# XMC4800-Misc.net
KiCad netlist of a schematic drawn in Altium Designer
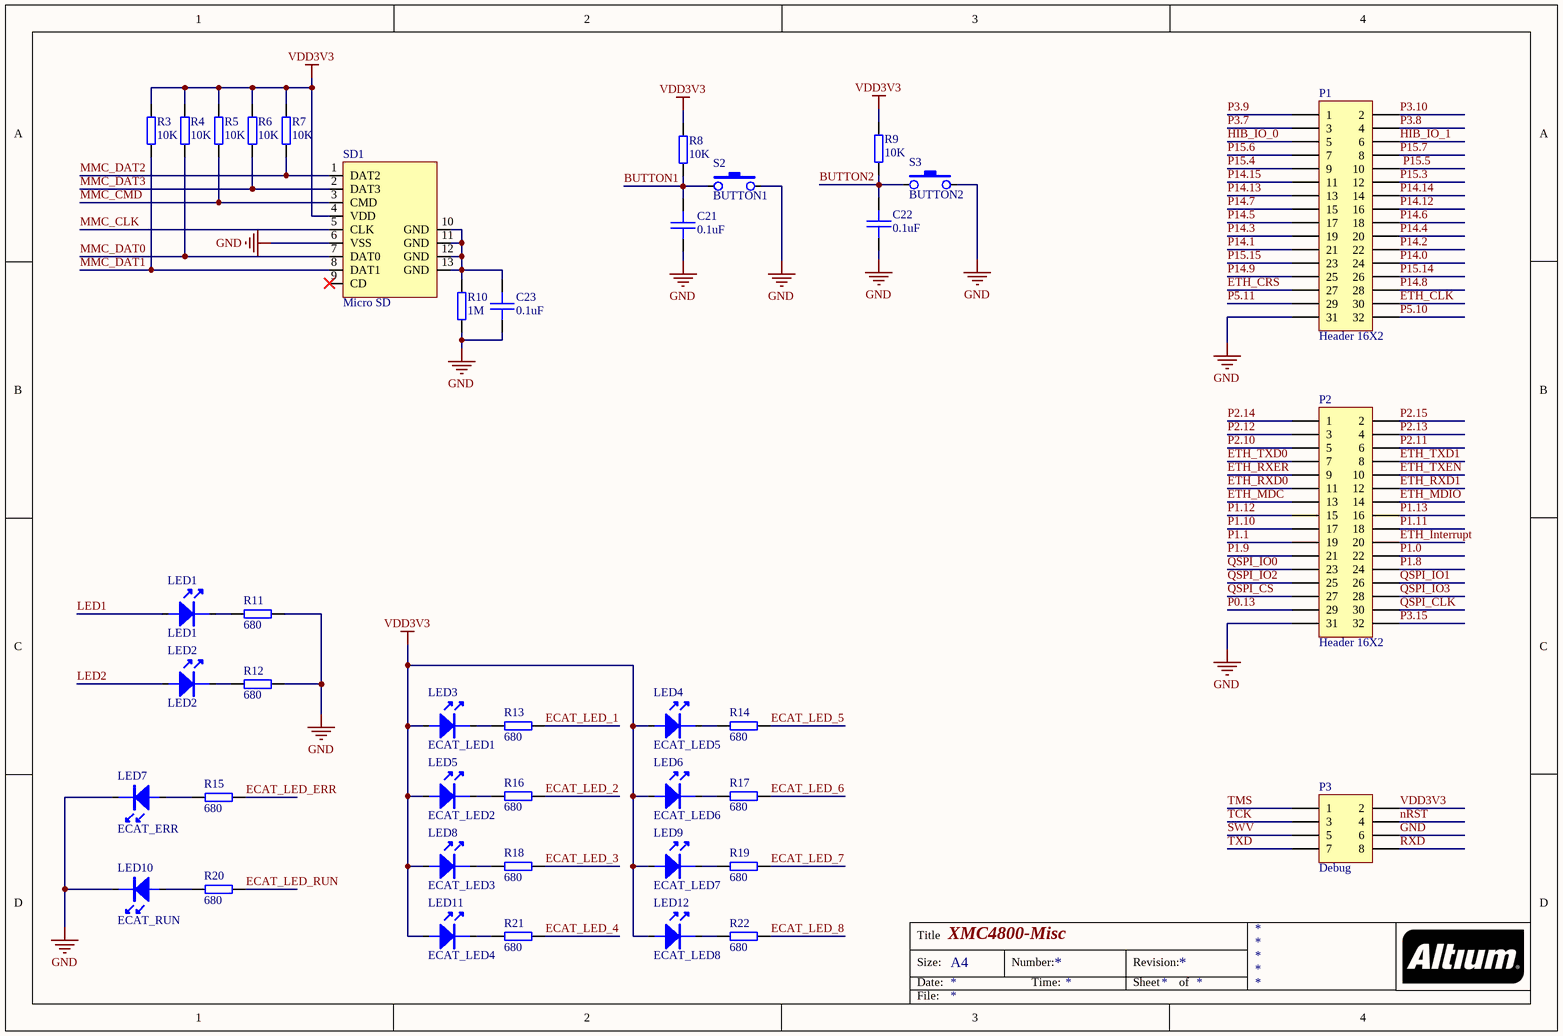
[diagram p0: XMC4800-Misc.SchDoc]

(export (version "E")
  (design (tool "Eeschema 10.0.6"))
  (components
    (comp (ref "C21")
      (value "0.1uF")
      (footprint "CAP-0603")
      (description "陶瓷贴片电容0603")
      (fields (field (name "TOLERANCE") "10%") (field (name "VOLTAGE") "50V"))
      (libsource (lib "momo") (part "C_0603"))
    )
    (comp (ref "C22")
      (value "0.1uF")
      (footprint "CAP-0603")
      (description "陶瓷贴片电容0603")
      (fields (field (name "TOLERANCE") "10%") (field (name "VOLTAGE") "50V"))
      (libsource (lib "momo") (part "C_0603"))
    )
    (comp (ref "C23")
      (value "0.1uF")
      (footprint "CAP-0603")
      (description "陶瓷贴片电容0603")
      (fields (field (name "TOLERANCE") "10%") (field (name "VOLTAGE") "50V"))
      (libsource (lib "momo") (part "C_0603"))
    )
    (comp (ref "LED1")
      (value "LED1")
      (footprint "LED_0603")
      (description "0603封装发光二极管")
      (libsource (lib "momo") (part "LED_0603"))
    )
    (comp (ref "LED2")
      (value "LED2")
      (footprint "LED_0603")
      (description "0603封装发光二极管")
      (libsource (lib "momo") (part "LED_0603"))
    )
    (comp (ref "LED3")
      (value "ECAT_LED1")
      (footprint "LED_0603")
      (description "0603封装发光二极管")
      (libsource (lib "momo") (part "LED_0603"))
    )
    (comp (ref "LED4")
      (value "ECAT_LED5")
      (footprint "LED_0603")
      (description "0603封装发光二极管")
      (libsource (lib "momo") (part "LED_0603"))
    )
    (comp (ref "LED5")
      (value "ECAT_LED2")
      (footprint "LED_0603")
      (description "0603封装发光二极管")
      (libsource (lib "momo") (part "LED_0603"))
    )
    (comp (ref "LED6")
      (value "ECAT_LED6")
      (footprint "LED_0603")
      (description "0603封装发光二极管")
      (libsource (lib "momo") (part "LED_0603"))
    )
    (comp (ref "LED7")
      (value "ECAT_ERR")
      (footprint "P-LCC-2")
      (description "3528封装发光二极管")
      (libsource (lib "momo") (part "LED_3528"))
    )
    (comp (ref "LED8")
      (value "ECAT_LED3")
      (footprint "LED_0603")
      (description "0603封装发光二极管")
      (libsource (lib "momo") (part "LED_0603"))
    )
    (comp (ref "LED9")
      (value "ECAT_LED7")
      (footprint "LED_0603")
      (description "0603封装发光二极管")
      (libsource (lib "momo") (part "LED_0603"))
    )
    (comp (ref "LED10")
      (value "ECAT_RUN")
      (footprint "P-LCC-2")
      (description "3528封装发光二极管")
      (libsource (lib "momo") (part "LED_3528"))
    )
    (comp (ref "LED11")
      (value "ECAT_LED4")
      (footprint "LED_0603")
      (description "0603封装发光二极管")
      (libsource (lib "momo") (part "LED_0603"))
    )
    (comp (ref "LED12")
      (value "ECAT_LED8")
      (footprint "LED_0603")
      (description "0603封装发光二极管")
      (libsource (lib "momo") (part "LED_0603"))
    )
    (comp (ref "P1")
      (value "Header 16X2")
      (footprint "HDR2X16")
      (description "Header, 16-Pin, Dual row")
      (fields (field (name "PUBLISHER") "Altium Limited"))
      (libsource (lib "Miscellaneous Connectors") (part "Header 16X2"))
    )
    (comp (ref "P2")
      (value "Header 16X2")
      (footprint "HDR2X16")
      (description "Header, 16-Pin, Dual row")
      (fields (field (name "PUBLISHER") "Altium Limited"))
      (libsource (lib "Miscellaneous Connectors") (part "Header 16X2"))
    )
    (comp (ref "P3")
      (value "Debug")
      (footprint "HDR2X4")
      (description "Header, 4-Pin, Dual row")
      (fields (field (name "PUBLISHER") "Altium Limited"))
      (libsource (lib "Miscellaneous Connectors") (part "Header 4X2"))
    )
    (comp (ref "R3")
      (value "10K")
      (footprint "RES-0603")
      (description "贴片电阻0603")
      (fields (field (name "TOLERANCE") "5%") (field (name "VOLTAGE") "50V"))
      (libsource (lib "momo") (part "R_0603"))
    )
    (comp (ref "R4")
      (value "10K")
      (footprint "RES-0603")
      (description "贴片电阻0603")
      (fields (field (name "TOLERANCE") "5%") (field (name "VOLTAGE") "50V"))
      (libsource (lib "momo") (part "R_0603"))
    )
    (comp (ref "R5")
      (value "10K")
      (footprint "RES-0603")
      (description "贴片电阻0603")
      (fields (field (name "TOLERANCE") "5%") (field (name "VOLTAGE") "50V"))
      (libsource (lib "momo") (part "R_0603"))
    )
    (comp (ref "R6")
      (value "10K")
      (footprint "RES-0603")
      (description "贴片电阻0603")
      (fields (field (name "TOLERANCE") "5%") (field (name "VOLTAGE") "50V"))
      (libsource (lib "momo") (part "R_0603"))
    )
    (comp (ref "R7")
      (value "10K")
      (footprint "RES-0603")
      (description "贴片电阻0603")
      (fields (field (name "TOLERANCE") "5%") (field (name "VOLTAGE") "50V"))
      (libsource (lib "momo") (part "R_0603"))
    )
    (comp (ref "R8")
      (value "10K")
      (footprint "RES-0603")
      (description "贴片电阻0603")
      (fields (field (name "TOLERANCE") "5%") (field (name "VOLTAGE") "50V"))
      (libsource (lib "momo") (part "R_0603"))
    )
    (comp (ref "R9")
      (value "10K")
      (footprint "RES-0603")
      (description "贴片电阻0603")
      (fields (field (name "TOLERANCE") "5%") (field (name "VOLTAGE") "50V"))
      (libsource (lib "momo") (part "R_0603"))
    )
    (comp (ref "R10")
      (value "1M")
      (footprint "RES-0603")
      (description "贴片电阻0603")
      (fields (field (name "TOLERANCE") "5%") (field (name "VOLTAGE") "50V"))
      (libsource (lib "momo") (part "R_0603"))
    )
    (comp (ref "R11")
      (value "680")
      (footprint "RES-0603")
      (description "贴片电阻0603")
      (fields (field (name "TOLERANCE") "5%") (field (name "VOLTAGE") "50V"))
      (libsource (lib "momo") (part "R_0603"))
    )
    (comp (ref "R12")
      (value "680")
      (footprint "RES-0603")
      (description "贴片电阻0603")
      (fields (field (name "TOLERANCE") "5%") (field (name "VOLTAGE") "50V"))
      (libsource (lib "momo") (part "R_0603"))
    )
    (comp (ref "R13")
      (value "680")
      (footprint "RES-0603")
      (description "贴片电阻0603")
      (fields (field (name "TOLERANCE") "5%") (field (name "VOLTAGE") "50V"))
      (libsource (lib "momo") (part "R_0603"))
    )
    (comp (ref "R14")
      (value "680")
      (footprint "RES-0603")
      (description "贴片电阻0603")
      (fields (field (name "TOLERANCE") "5%") (field (name "VOLTAGE") "50V"))
      (libsource (lib "momo") (part "R_0603"))
    )
    (comp (ref "R15")
      (value "680")
      (footprint "RES-0603")
      (description "贴片电阻0603")
      (fields (field (name "TOLERANCE") "5%") (field (name "VOLTAGE") "50V"))
      (libsource (lib "momo") (part "R_0603"))
    )
    (comp (ref "R16")
      (value "680")
      (footprint "RES-0603")
      (description "贴片电阻0603")
      (fields (field (name "TOLERANCE") "5%") (field (name "VOLTAGE") "50V"))
      (libsource (lib "momo") (part "R_0603"))
    )
    (comp (ref "R17")
      (value "680")
      (footprint "RES-0603")
      (description "贴片电阻0603")
      (fields (field (name "TOLERANCE") "5%") (field (name "VOLTAGE") "50V"))
      (libsource (lib "momo") (part "R_0603"))
    )
    (comp (ref "R18")
      (value "680")
      (footprint "RES-0603")
      (description "贴片电阻0603")
      (fields (field (name "TOLERANCE") "5%") (field (name "VOLTAGE") "50V"))
      (libsource (lib "momo") (part "R_0603"))
    )
    (comp (ref "R19")
      (value "680")
      (footprint "RES-0603")
      (description "贴片电阻0603")
      (fields (field (name "TOLERANCE") "5%") (field (name "VOLTAGE") "50V"))
      (libsource (lib "momo") (part "R_0603"))
    )
    (comp (ref "R20")
      (value "680")
      (footprint "RES-0603")
      (description "贴片电阻0603")
      (fields (field (name "TOLERANCE") "5%") (field (name "VOLTAGE") "50V"))
      (libsource (lib "momo") (part "R_0603"))
    )
    (comp (ref "R21")
      (value "680")
      (footprint "RES-0603")
      (description "贴片电阻0603")
      (fields (field (name "TOLERANCE") "5%") (field (name "VOLTAGE") "50V"))
      (libsource (lib "momo") (part "R_0603"))
    )
    (comp (ref "R22")
      (value "680")
      (footprint "RES-0603")
      (description "贴片电阻0603")
      (fields (field (name "TOLERANCE") "5%") (field (name "VOLTAGE") "50V"))
      (libsource (lib "momo") (part "R_0603"))
    )
    (comp (ref "S2")
      (value "BUTTON1")
      (footprint "KEY_3X4X2")
      (description "轻触开关3X4X2")
      (libsource (lib "momo") (part "KEY"))
    )
    (comp (ref "S3")
      (value "BUTTON2")
      (footprint "KEY_3X4X2")
      (description "轻触开关3X4X2")
      (libsource (lib "momo") (part "KEY"))
    )
    (comp (ref "SD1")
      (value "Micro SD")
      (footprint "7MSDP-B0-1012")
      (description "Micro SD卡座")
      (libsource (lib "momo") (part "Micro SD"))
    )
  )
  (nets
    (net (code "1") (name "/BUTTON1") (class "Default")
      (node (ref "C21") (pin "1") (pinfunction "1_1") (pintype "passive"))
      (node (ref "R8") (pin "1") (pinfunction "1_1") (pintype "passive"))
      (node (ref "S2") (pin "1") (pinfunction "1_1") (pintype "passive"))
    )
    (net (code "2") (name "/BUTTON2") (class "Default")
      (node (ref "C22") (pin "1") (pinfunction "1_1") (pintype "passive"))
      (node (ref "R9") (pin "1") (pinfunction "1_1") (pintype "passive"))
      (node (ref "S3") (pin "1") (pinfunction "1_1") (pintype "passive"))
    )
    (net (code "3") (name "/ECAT_LED_1") (class "Default")
      (node (ref "R13") (pin "2") (pinfunction "2_2") (pintype "passive"))
    )
    (net (code "4") (name "/ECAT_LED_2") (class "Default")
      (node (ref "R16") (pin "2") (pinfunction "2_2") (pintype "passive"))
    )
    (net (code "5") (name "/ECAT_LED_3") (class "Default")
      (node (ref "R18") (pin "2") (pinfunction "2_2") (pintype "passive"))
    )
    (net (code "6") (name "/ECAT_LED_4") (class "Default")
      (node (ref "R21") (pin "2") (pinfunction "2_2") (pintype "passive"))
    )
    (net (code "7") (name "/ECAT_LED_5") (class "Default")
      (node (ref "R14") (pin "2") (pinfunction "2_2") (pintype "passive"))
    )
    (net (code "8") (name "/ECAT_LED_6") (class "Default")
      (node (ref "R17") (pin "2") (pinfunction "2_2") (pintype "passive"))
    )
    (net (code "9") (name "/ECAT_LED_7") (class "Default")
      (node (ref "R19") (pin "2") (pinfunction "2_2") (pintype "passive"))
    )
    (net (code "10") (name "/ECAT_LED_8") (class "Default")
      (node (ref "R22") (pin "2") (pinfunction "2_2") (pintype "passive"))
    )
    (net (code "11") (name "/ECAT_LED_ERR") (class "Default")
      (node (ref "R15") (pin "2") (pinfunction "2_2") (pintype "passive"))
    )
    (net (code "12") (name "/ECAT_LED_RUN") (class "Default")
      (node (ref "R20") (pin "2") (pinfunction "2_2") (pintype "passive"))
    )
    (net (code "13") (name "/ETH_CLK") (class "Default")
      (node (ref "P1") (pin "30") (pinfunction "30_30") (pintype "passive"))
    )
    (net (code "14") (name "/ETH_CRS") (class "Default")
      (node (ref "P1") (pin "27") (pinfunction "27_27") (pintype "passive"))
    )
    (net (code "15") (name "/ETH_Interrupt") (class "Default")
      (node (ref "P2") (pin "20") (pinfunction "20_20") (pintype "passive"))
    )
    (net (code "16") (name "/ETH_MDC") (class "Default")
      (node (ref "P2") (pin "13") (pinfunction "13_13") (pintype "passive"))
    )
    (net (code "17") (name "/ETH_MDIO") (class "Default")
      (node (ref "P2") (pin "14") (pinfunction "14_14") (pintype "passive"))
    )
    (net (code "18") (name "/ETH_RXD0") (class "Default")
      (node (ref "P2") (pin "11") (pinfunction "11_11") (pintype "passive"))
    )
    (net (code "19") (name "/ETH_RXD1") (class "Default")
      (node (ref "P2") (pin "12") (pinfunction "12_12") (pintype "passive"))
    )
    (net (code "20") (name "/ETH_RXER") (class "Default")
      (node (ref "P2") (pin "9") (pinfunction "9_9") (pintype "passive"))
    )
    (net (code "21") (name "/ETH_TXD0") (class "Default")
      (node (ref "P2") (pin "7") (pinfunction "7_7") (pintype "passive"))
    )
    (net (code "22") (name "/ETH_TXD1") (class "Default")
      (node (ref "P2") (pin "8") (pinfunction "8_8") (pintype "passive"))
    )
    (net (code "23") (name "/ETH_TXEN") (class "Default")
      (node (ref "P2") (pin "10") (pinfunction "10_10") (pintype "passive"))
    )
    (net (code "24") (name "/HIB_IO_0") (class "Default")
      (node (ref "P1") (pin "5") (pinfunction "5_5") (pintype "passive"))
    )
    (net (code "25") (name "/HIB_IO_1") (class "Default")
      (node (ref "P1") (pin "6") (pinfunction "6_6") (pintype "passive"))
    )
    (net (code "26") (name "/LED1") (class "Default")
      (node (ref "LED1") (pin "1") (pinfunction "A_1") (pintype "passive"))
    )
    (net (code "27") (name "/LED2") (class "Default")
      (node (ref "LED2") (pin "1") (pinfunction "A_1") (pintype "passive"))
    )
    (net (code "28") (name "/MMC_CLK") (class "Default")
      (node (ref "SD1") (pin "5") (pinfunction "CLK_5") (pintype "passive"))
    )
    (net (code "29") (name "/MMC_CMD") (class "Default")
      (node (ref "R5") (pin "1") (pinfunction "1_1") (pintype "passive"))
      (node (ref "SD1") (pin "3") (pinfunction "CMD_3") (pintype "passive"))
    )
    (net (code "30") (name "/MMC_DAT0") (class "Default")
      (node (ref "R4") (pin "1") (pinfunction "1_1") (pintype "passive"))
      (node (ref "SD1") (pin "7") (pinfunction "DAT0_7") (pintype "passive"))
    )
    (net (code "31") (name "/MMC_DAT1") (class "Default")
      (node (ref "R3") (pin "1") (pinfunction "1_1") (pintype "passive"))
      (node (ref "SD1") (pin "8") (pinfunction "DAT1_8") (pintype "passive"))
    )
    (net (code "32") (name "/MMC_DAT2") (class "Default")
      (node (ref "R7") (pin "1") (pinfunction "1_1") (pintype "passive"))
      (node (ref "SD1") (pin "1") (pinfunction "DAT2_1") (pintype "passive"))
    )
    (net (code "33") (name "/MMC_DAT3") (class "Default")
      (node (ref "R6") (pin "1") (pinfunction "1_1") (pintype "passive"))
      (node (ref "SD1") (pin "2") (pinfunction "DAT3_2") (pintype "passive"))
    )
    (net (code "34") (name "/P0.13") (class "Default")
      (node (ref "P2") (pin "29") (pinfunction "29_29") (pintype "passive"))
    )
    (net (code "35") (name "/P1.0") (class "Default")
      (node (ref "P2") (pin "22") (pinfunction "22_22") (pintype "passive"))
    )
    (net (code "36") (name "/P1.1") (class "Default")
      (node (ref "P2") (pin "19") (pinfunction "19_19") (pintype "passive"))
    )
    (net (code "37") (name "/P1.8") (class "Default")
      (node (ref "P2") (pin "24") (pinfunction "24_24") (pintype "passive"))
    )
    (net (code "38") (name "/P1.9") (class "Default")
      (node (ref "P2") (pin "21") (pinfunction "21_21") (pintype "passive"))
    )
    (net (code "39") (name "/P1.10") (class "Default")
      (node (ref "P2") (pin "17") (pinfunction "17_17") (pintype "passive"))
    )
    (net (code "40") (name "/P1.11") (class "Default")
      (node (ref "P2") (pin "18") (pinfunction "18_18") (pintype "passive"))
    )
    (net (code "41") (name "/P1.12") (class "Default")
      (node (ref "P2") (pin "15") (pinfunction "15_15") (pintype "passive"))
    )
    (net (code "42") (name "/P1.13") (class "Default")
      (node (ref "P2") (pin "16") (pinfunction "16_16") (pintype "passive"))
    )
    (net (code "43") (name "/P2.10") (class "Default")
      (node (ref "P2") (pin "5") (pinfunction "5_5") (pintype "passive"))
    )
    (net (code "44") (name "/P2.11") (class "Default")
      (node (ref "P2") (pin "6") (pinfunction "6_6") (pintype "passive"))
    )
    (net (code "45") (name "/P2.12") (class "Default")
      (node (ref "P2") (pin "3") (pinfunction "3_3") (pintype "passive"))
    )
    (net (code "46") (name "/P2.13") (class "Default")
      (node (ref "P2") (pin "4") (pinfunction "4_4") (pintype "passive"))
    )
    (net (code "47") (name "/P2.14") (class "Default")
      (node (ref "P2") (pin "1") (pinfunction "1_1") (pintype "passive"))
    )
    (net (code "48") (name "/P2.15") (class "Default")
      (node (ref "P2") (pin "2") (pinfunction "2_2") (pintype "passive"))
    )
    (net (code "49") (name "/P3.7") (class "Default")
      (node (ref "P1") (pin "3") (pinfunction "3_3") (pintype "passive"))
    )
    (net (code "50") (name "/P3.8") (class "Default")
      (node (ref "P1") (pin "4") (pinfunction "4_4") (pintype "passive"))
    )
    (net (code "51") (name "/P3.9") (class "Default")
      (node (ref "P1") (pin "1") (pinfunction "1_1") (pintype "passive"))
    )
    (net (code "52") (name "/P3.10") (class "Default")
      (node (ref "P1") (pin "2") (pinfunction "2_2") (pintype "passive"))
    )
    (net (code "53") (name "/P3.15") (class "Default")
      (node (ref "P2") (pin "32") (pinfunction "32_32") (pintype "passive"))
    )
    (net (code "54") (name "/P5.10") (class "Default")
      (node (ref "P1") (pin "32") (pinfunction "32_32") (pintype "passive"))
    )
    (net (code "55") (name "/P5.11") (class "Default")
      (node (ref "P1") (pin "29") (pinfunction "29_29") (pintype "passive"))
    )
    (net (code "56") (name "/P14.0") (class "Default")
      (node (ref "P1") (pin "24") (pinfunction "24_24") (pintype "passive"))
    )
    (net (code "57") (name "/P14.1") (class "Default")
      (node (ref "P1") (pin "21") (pinfunction "21_21") (pintype "passive"))
    )
    (net (code "58") (name "/P14.2") (class "Default")
      (node (ref "P1") (pin "22") (pinfunction "22_22") (pintype "passive"))
    )
    (net (code "59") (name "/P14.3") (class "Default")
      (node (ref "P1") (pin "19") (pinfunction "19_19") (pintype "passive"))
    )
    (net (code "60") (name "/P14.4") (class "Default")
      (node (ref "P1") (pin "20") (pinfunction "20_20") (pintype "passive"))
    )
    (net (code "61") (name "/P14.5") (class "Default")
      (node (ref "P1") (pin "17") (pinfunction "17_17") (pintype "passive"))
    )
    (net (code "62") (name "/P14.6") (class "Default")
      (node (ref "P1") (pin "18") (pinfunction "18_18") (pintype "passive"))
    )
    (net (code "63") (name "/P14.7") (class "Default")
      (node (ref "P1") (pin "15") (pinfunction "15_15") (pintype "passive"))
    )
    (net (code "64") (name "/P14.8") (class "Default")
      (node (ref "P1") (pin "28") (pinfunction "28_28") (pintype "passive"))
    )
    (net (code "65") (name "/P14.9") (class "Default")
      (node (ref "P1") (pin "25") (pinfunction "25_25") (pintype "passive"))
    )
    (net (code "66") (name "/P14.12") (class "Default")
      (node (ref "P1") (pin "16") (pinfunction "16_16") (pintype "passive"))
    )
    (net (code "67") (name "/P14.13") (class "Default")
      (node (ref "P1") (pin "13") (pinfunction "13_13") (pintype "passive"))
    )
    (net (code "68") (name "/P14.14") (class "Default")
      (node (ref "P1") (pin "14") (pinfunction "14_14") (pintype "passive"))
    )
    (net (code "69") (name "/P14.15") (class "Default")
      (node (ref "P1") (pin "11") (pinfunction "11_11") (pintype "passive"))
    )
    (net (code "70") (name "/P15.3") (class "Default")
      (node (ref "P1") (pin "12") (pinfunction "12_12") (pintype "passive"))
    )
    (net (code "71") (name "/P15.4") (class "Default")
      (node (ref "P1") (pin "9") (pinfunction "9_9") (pintype "passive"))
    )
    (net (code "72") (name "/P15.5") (class "Default")
      (node (ref "P1") (pin "10") (pinfunction "10_10") (pintype "passive"))
    )
    (net (code "73") (name "/P15.6") (class "Default")
      (node (ref "P1") (pin "7") (pinfunction "7_7") (pintype "passive"))
    )
    (net (code "74") (name "/P15.7") (class "Default")
      (node (ref "P1") (pin "8") (pinfunction "8_8") (pintype "passive"))
    )
    (net (code "75") (name "/P15.14") (class "Default")
      (node (ref "P1") (pin "26") (pinfunction "26_26") (pintype "passive"))
    )
    (net (code "76") (name "/P15.15") (class "Default")
      (node (ref "P1") (pin "23") (pinfunction "23_23") (pintype "passive"))
    )
    (net (code "77") (name "/QSPI_CLK") (class "Default")
      (node (ref "P2") (pin "30") (pinfunction "30_30") (pintype "passive"))
    )
    (net (code "78") (name "/QSPI_CS") (class "Default")
      (node (ref "P2") (pin "27") (pinfunction "27_27") (pintype "passive"))
    )
    (net (code "79") (name "/QSPI_IO0") (class "Default")
      (node (ref "P2") (pin "23") (pinfunction "23_23") (pintype "passive"))
    )
    (net (code "80") (name "/QSPI_IO1") (class "Default")
      (node (ref "P2") (pin "26") (pinfunction "26_26") (pintype "passive"))
    )
    (net (code "81") (name "/QSPI_IO2") (class "Default")
      (node (ref "P2") (pin "25") (pinfunction "25_25") (pintype "passive"))
    )
    (net (code "82") (name "/QSPI_IO3") (class "Default")
      (node (ref "P2") (pin "28") (pinfunction "28_28") (pintype "passive"))
    )
    (net (code "83") (name "/RXD") (class "Default")
      (node (ref "P3") (pin "8") (pinfunction "8_8") (pintype "passive"))
    )
    (net (code "84") (name "/SWV") (class "Default")
      (node (ref "P3") (pin "5") (pinfunction "5_5") (pintype "passive"))
    )
    (net (code "85") (name "/TCK") (class "Default")
      (node (ref "P3") (pin "3") (pinfunction "3_3") (pintype "passive"))
    )
    (net (code "86") (name "/TMS") (class "Default")
      (node (ref "P3") (pin "1") (pinfunction "1_1") (pintype "passive"))
    )
    (net (code "87") (name "/TXD") (class "Default")
      (node (ref "P3") (pin "7") (pinfunction "7_7") (pintype "passive"))
    )
    (net (code "88") (name "/nRST") (class "Default")
      (node (ref "P3") (pin "4") (pinfunction "4_4") (pintype "passive"))
    )
    (net (code "89") (name "GND") (class "Default")
      (node (ref "C21") (pin "2") (pinfunction "2_2") (pintype "passive"))
      (node (ref "C22") (pin "2") (pinfunction "2_2") (pintype "passive"))
      (node (ref "C23") (pin "2") (pinfunction "2_2") (pintype "passive"))
      (node (ref "LED10") (pin "C") (pinfunction "K_C") (pintype "passive"))
      (node (ref "LED7") (pin "C") (pinfunction "K_C") (pintype "passive"))
      (node (ref "P1") (pin "31") (pinfunction "31_31") (pintype "passive"))
      (node (ref "P2") (pin "31") (pinfunction "31_31") (pintype "passive"))
      (node (ref "P3") (pin "6") (pinfunction "6_6") (pintype "passive"))
      (node (ref "R10") (pin "1") (pinfunction "1_1") (pintype "passive"))
      (node (ref "R11") (pin "2") (pinfunction "2_2") (pintype "passive"))
      (node (ref "R12") (pin "2") (pinfunction "2_2") (pintype "passive"))
      (node (ref "S2") (pin "2") (pinfunction "2_2") (pintype "passive"))
      (node (ref "S3") (pin "2") (pinfunction "2_2") (pintype "passive"))
      (node (ref "SD1") (pin "6") (pinfunction "VSS_6") (pintype "passive"))
    )
    (net (code "90") (name "Net-(C23-Pad1)") (class "Default")
      (node (ref "C23") (pin "1") (pinfunction "1_1") (pintype "passive"))
      (node (ref "R10") (pin "2") (pinfunction "2_2") (pintype "passive"))
      (node (ref "SD1") (pin "10") (pinfunction "GND_10") (pintype "passive"))
      (node (ref "SD1") (pin "11") (pinfunction "GND_11") (pintype "passive"))
      (node (ref "SD1") (pin "12") (pinfunction "GND_12") (pintype "passive"))
      (node (ref "SD1") (pin "13") (pinfunction "GND_13") (pintype "passive"))
    )
    (net (code "91") (name "Net-(LED1-K)") (class "Default")
      (node (ref "LED1") (pin "2") (pinfunction "K_2") (pintype "passive"))
      (node (ref "R11") (pin "1") (pinfunction "1_1") (pintype "passive"))
    )
    (net (code "92") (name "Net-(LED2-K)") (class "Default")
      (node (ref "LED2") (pin "2") (pinfunction "K_2") (pintype "passive"))
      (node (ref "R12") (pin "1") (pinfunction "1_1") (pintype "passive"))
    )
    (net (code "93") (name "Net-(LED3-K)") (class "Default")
      (node (ref "LED3") (pin "2") (pinfunction "K_2") (pintype "passive"))
      (node (ref "R13") (pin "1") (pinfunction "1_1") (pintype "passive"))
    )
    (net (code "94") (name "Net-(LED4-K)") (class "Default")
      (node (ref "LED4") (pin "2") (pinfunction "K_2") (pintype "passive"))
      (node (ref "R14") (pin "1") (pinfunction "1_1") (pintype "passive"))
    )
    (net (code "95") (name "Net-(LED5-K)") (class "Default")
      (node (ref "LED5") (pin "2") (pinfunction "K_2") (pintype "passive"))
      (node (ref "R16") (pin "1") (pinfunction "1_1") (pintype "passive"))
    )
    (net (code "96") (name "Net-(LED6-K)") (class "Default")
      (node (ref "LED6") (pin "2") (pinfunction "K_2") (pintype "passive"))
      (node (ref "R17") (pin "1") (pinfunction "1_1") (pintype "passive"))
    )
    (net (code "97") (name "Net-(LED7-PadA)") (class "Default")
      (node (ref "LED7") (pin "A") (pinfunction "A_A") (pintype "passive"))
      (node (ref "R15") (pin "1") (pinfunction "1_1") (pintype "passive"))
    )
    (net (code "98") (name "Net-(LED8-K)") (class "Default")
      (node (ref "LED8") (pin "2") (pinfunction "K_2") (pintype "passive"))
      (node (ref "R18") (pin "1") (pinfunction "1_1") (pintype "passive"))
    )
    (net (code "99") (name "Net-(LED9-K)") (class "Default")
      (node (ref "LED9") (pin "2") (pinfunction "K_2") (pintype "passive"))
      (node (ref "R19") (pin "1") (pinfunction "1_1") (pintype "passive"))
    )
    (net (code "100") (name "Net-(LED10-PadA)") (class "Default")
      (node (ref "LED10") (pin "A") (pinfunction "A_A") (pintype "passive"))
      (node (ref "R20") (pin "1") (pinfunction "1_1") (pintype "passive"))
    )
    (net (code "101") (name "Net-(LED11-K)") (class "Default")
      (node (ref "LED11") (pin "2") (pinfunction "K_2") (pintype "passive"))
      (node (ref "R21") (pin "1") (pinfunction "1_1") (pintype "passive"))
    )
    (net (code "102") (name "Net-(LED12-K)") (class "Default")
      (node (ref "LED12") (pin "2") (pinfunction "K_2") (pintype "passive"))
      (node (ref "R22") (pin "1") (pinfunction "1_1") (pintype "passive"))
    )
    (net (code "103") (name "VDD3V3") (class "Default")
      (node (ref "LED11") (pin "1") (pinfunction "A_1") (pintype "passive"))
      (node (ref "LED12") (pin "1") (pinfunction "A_1") (pintype "passive"))
      (node (ref "LED3") (pin "1") (pinfunction "A_1") (pintype "passive"))
      (node (ref "LED4") (pin "1") (pinfunction "A_1") (pintype "passive"))
      (node (ref "LED5") (pin "1") (pinfunction "A_1") (pintype "passive"))
      (node (ref "LED6") (pin "1") (pinfunction "A_1") (pintype "passive"))
      (node (ref "LED8") (pin "1") (pinfunction "A_1") (pintype "passive"))
      (node (ref "LED9") (pin "1") (pinfunction "A_1") (pintype "passive"))
      (node (ref "P3") (pin "2") (pinfunction "2_2") (pintype "passive"))
      (node (ref "R3") (pin "2") (pinfunction "2_2") (pintype "passive"))
      (node (ref "R4") (pin "2") (pinfunction "2_2") (pintype "passive"))
      (node (ref "R5") (pin "2") (pinfunction "2_2") (pintype "passive"))
      (node (ref "R6") (pin "2") (pinfunction "2_2") (pintype "passive"))
      (node (ref "R7") (pin "2") (pinfunction "2_2") (pintype "passive"))
      (node (ref "R8") (pin "2") (pinfunction "2_2") (pintype "passive"))
      (node (ref "R9") (pin "2") (pinfunction "2_2") (pintype "passive"))
      (node (ref "SD1") (pin "4") (pinfunction "VDD_4") (pintype "passive"))
    )
    (net (code "104") (name "unconnected-(SD1-CD-Pad9)") (class "Default")
      (node (ref "SD1") (pin "9") (pinfunction "CD_9") (pintype "passive+no_connect"))
    )
  )
)
